# Supply_5V0.net
KiCad netlist of a schematic drawn in Altium Designer
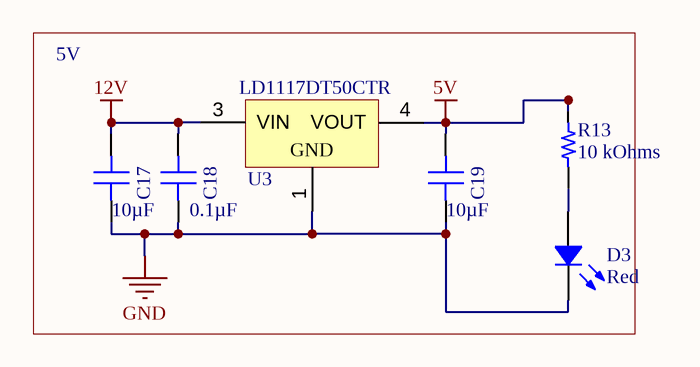
[diagram p0: Supply_5V0.SchDoc]

(export (version "E")
  (design (tool "Eeschema 10.0.6"))
  (components
    (comp (ref "C17")
      (value "10µF")
      (footprint "CAP 0805_2012")
      (description "CAP CER 10UF 16V X5R 0805")
      (fields (field (name "TOLERANCE") "±10%") (field (name "PART NUMBER") "0805YD106KAT2A"))
      (libsource (lib "Celestial Altium Library - altium_library") (part "Capacitor"))
    )
    (comp (ref "C18")
      (value "~")
      (footprint "CAP 0805_2012")
      (description "CAP CER 0.1UF 25V Z5U 0805")
      (fields
        (field (name "TOLERANCE") "-20%, +80%")
        (field (name "PART NUMBER") "08053E104ZAT2A")
        (field (name "CAPACITANCE") "0.1µF")
      )
      (libsource (lib "Celestial Altium Library - altium_library") (part "Capacitor"))
    )
    (comp (ref "C19")
      (value "10µF")
      (footprint "CAP 0805_2012")
      (description "CAP CER 10UF 16V X5R 0805")
      (fields (field (name "TOLERANCE") "±10%") (field (name "PART NUMBER") "0805YD106KAT2A"))
      (libsource (lib "Celestial Altium Library - altium_library") (part "Capacitor"))
    )
    (comp (ref "D3")
      (value "Red")
      (footprint "LED 0603_1608 RED")
      (description "LED RED CLEAR 0603 SMD")
      (fields
        (field (name "PART NUMBER") "LR Q976.01-P2R2-1")
        (field (name "MANUFACTURER") "ams-OSRAM USA Inc.")
      )
      (libsource (lib "Celestial Altium Library - altium_library") (part "LED"))
    )
    (comp (ref "R13")
      (value "10 kOhms")
      (footprint "YAGEO RES 0603_1608")
      (description "RES SMD 10K OHM 5% 1/10W 0603")
      (fields (field (name "PART NUMBER") "AC0603JR-0710KL") (field (name "MANUFACTURER") "Yageo"))
      (libsource (lib "Celestial Altium Library - altium_library") (part "Resistor"))
    )
    (comp (ref "U3")
      (value "LD1117DT50CTR")
      (footprint "LD1117DT:DPAK456P1010X240-3N")
      (description "Fixed Low Drop Positive Voltage Regulator, 5V, 3-Pin DPAK, Tape and Reel")
      (libsource (lib "LD1117DT50CTR") (part "LD1117DT50CTR"))
    )
  )
  (nets
    (net (code "1") (name "5V") (class "Default")
      (node (ref "C19") (pin "1") (pinfunction "1_1") (pintype "passive"))
      (node (ref "R13") (pin "2") (pinfunction "2_2") (pintype "passive"))
      (node (ref "U3") (pin "4") (pinfunction "VOUT_4") (pintype "power_in"))
    )
    (net (code "2") (name "12V") (class "Default")
      (node (ref "C17") (pin "1") (pinfunction "1_1") (pintype "passive"))
      (node (ref "C18") (pin "1") (pinfunction "1_1") (pintype "passive"))
      (node (ref "U3") (pin "3") (pinfunction "VIN_3") (pintype "power_in"))
    )
    (net (code "3") (name "GND") (class "Default")
      (node (ref "C17") (pin "2") (pinfunction "2_2") (pintype "passive"))
      (node (ref "C18") (pin "2") (pinfunction "2_2") (pintype "passive"))
      (node (ref "C19") (pin "2") (pinfunction "2_2") (pintype "passive"))
      (node (ref "D3") (pin "2") (pinfunction "2_2") (pintype "passive"))
      (node (ref "U3") (pin "1") (pinfunction "GND_1") (pintype "power_in"))
    )
    (net (code "4") (name "Net-(D3-Pad1)") (class "Default")
      (node (ref "D3") (pin "1") (pinfunction "1_1") (pintype "passive"))
      (node (ref "R13") (pin "1") (pinfunction "1_1") (pintype "passive"))
    )
  )
)
